# ComboBreaker.net
KiCad netlist of a schematic drawn in EAGLE
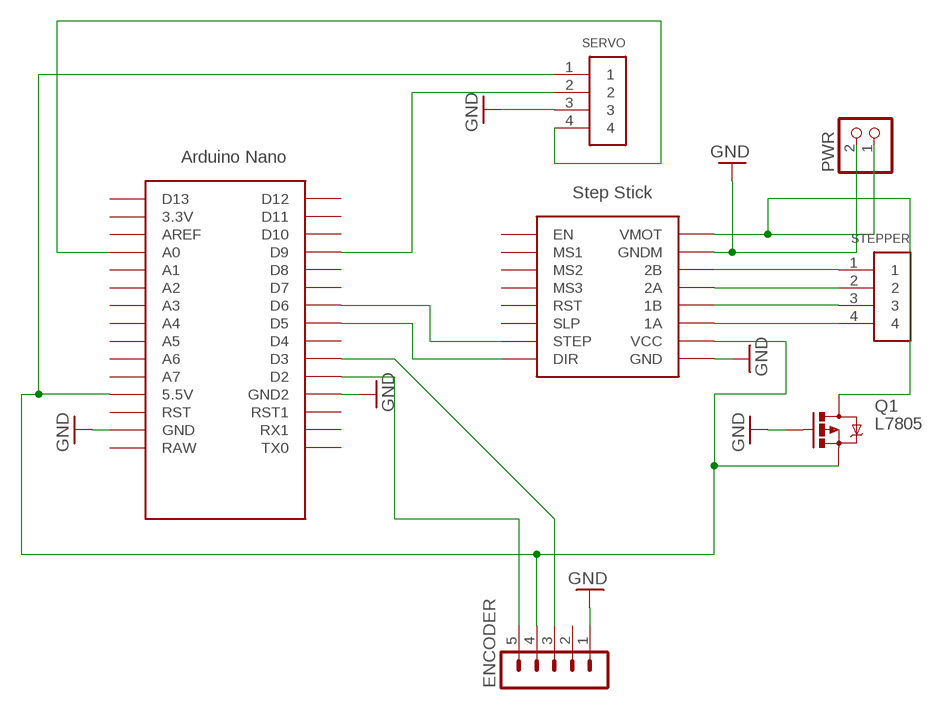
[diagram p0: schematic, sheet 1]

(export (version "E")
  (design (tool "Eeschema 10.0.6"))
  (components
    (comp (ref "ENCODER")
      (value "MA05-1")
      (footprint "eagle-import:MA05-1")
      (libsource (lib "eagle-import") (part "MA05-1"))
    )
    (comp (ref "PWR")
      (value "JST_2PIN-SMT")
      (footprint "eagle-import:JST-PH-2-SMT")
      (libsource (lib "eagle-import") (part "JST_2PIN-SMT"))
    )
    (comp (ref "Q1")
      (value "L7805")
      (footprint "eagle-import:TO220V")
      (libsource (lib "eagle-import") (part "MOSFET-PCHANNELFQP27P06"))
    )
    (comp (ref "SERVO")
      (value "1X4-BIG")
      (footprint "eagle-import:1X04-BIG")
      (libsource (lib "eagle-import") (part "1X4-BIG"))
    )
    (comp (ref "STEPPER")
      (value "1X4-BIG")
      (footprint "eagle-import:1X04-BIG")
      (libsource (lib "eagle-import") (part "1X4-BIG"))
    )
    (comp (ref "U$1")
      (value "NANO")
      (footprint "eagle-import:NANO")
      (libsource (lib "eagle-import") (part "NANO"))
    )
    (comp (ref "U$2")
      (value "STEP-STICK")
      (footprint "eagle-import:STEP-STICK")
      (libsource (lib "eagle-import") (part "STEP-STICK"))
    )
  )
  (nets
    (net (code "1") (name "GND") (class "Default")
      (node (ref "ENCODER") (pin "1") (pinfunction "1_1") (pintype "passive"))
      (node (ref "PWR") (pin "2") (pinfunction "1_2") (pintype "passive"))
      (node (ref "Q1") (pin "1") (pinfunction "G_1") (pintype "passive"))
      (node (ref "SERVO") (pin "3") (pinfunction "3_3") (pintype "bidirectional"))
      (node (ref "U$1") (pin "GND") (pinfunction "GND_GND") (pintype "bidirectional"))
      (node (ref "U$1") (pin "GND1") (pinfunction "GND2_GND1") (pintype "bidirectional"))
      (node (ref "U$2") (pin "GND") (pinfunction "GND_GND") (pintype "bidirectional"))
      (node (ref "U$2") (pin "GNDM") (pinfunction "GNDM_GNDM") (pintype "bidirectional"))
    )
    (net (code "2") (name "Net-(ENCODER-Pad3)") (class "Default")
      (node (ref "ENCODER") (pin "3") (pinfunction "3_3") (pintype "passive"))
      (node (ref "U$1") (pin "D3") (pinfunction "D3_D3") (pintype "bidirectional"))
    )
    (net (code "3") (name "Net-(ENCODER-Pad5)") (class "Default")
      (node (ref "ENCODER") (pin "5") (pinfunction "5_5") (pintype "passive"))
      (node (ref "U$1") (pin "D2") (pinfunction "D2_D2") (pintype "bidirectional"))
    )
    (net (code "4") (name "Net-(PWR-2)") (class "Default")
      (node (ref "PWR") (pin "1") (pinfunction "2_1") (pintype "passive"))
      (node (ref "Q1") (pin "2") (pinfunction "D_2") (pintype "passive"))
      (node (ref "U$2") (pin "VMOT") (pinfunction "VMOT_VMOT") (pintype "bidirectional"))
    )
    (net (code "5") (name "Net-(Q1-S)") (class "Default")
      (node (ref "ENCODER") (pin "4") (pinfunction "4_4") (pintype "passive"))
      (node (ref "Q1") (pin "3") (pinfunction "S_3") (pintype "passive"))
      (node (ref "SERVO") (pin "1") (pinfunction "1_1") (pintype "bidirectional"))
      (node (ref "U$1") (pin "5V") (pinfunction "5.5V_5V") (pintype "bidirectional"))
      (node (ref "U$2") (pin "VCC") (pinfunction "VCC_VCC") (pintype "bidirectional"))
    )
    (net (code "6") (name "Net-(SERVO-Pad2)") (class "Default")
      (node (ref "SERVO") (pin "2") (pinfunction "2_2") (pintype "bidirectional"))
      (node (ref "U$1") (pin "D9") (pinfunction "D9_D9") (pintype "bidirectional"))
    )
    (net (code "7") (name "Net-(SERVO-Pad4)") (class "Default")
      (node (ref "SERVO") (pin "4") (pinfunction "4_4") (pintype "bidirectional"))
      (node (ref "U$1") (pin "A0") (pinfunction "A0_A0") (pintype "bidirectional"))
    )
    (net (code "8") (name "Net-(STEPPER-Pad1)") (class "Default")
      (node (ref "STEPPER") (pin "1") (pinfunction "1_1") (pintype "bidirectional"))
      (node (ref "U$2") (pin "2B") (pinfunction "2B_2B") (pintype "bidirectional"))
    )
    (net (code "9") (name "Net-(STEPPER-Pad2)") (class "Default")
      (node (ref "STEPPER") (pin "2") (pinfunction "2_2") (pintype "bidirectional"))
      (node (ref "U$2") (pin "2A") (pinfunction "2A_2A") (pintype "bidirectional"))
    )
    (net (code "10") (name "Net-(STEPPER-Pad3)") (class "Default")
      (node (ref "STEPPER") (pin "3") (pinfunction "3_3") (pintype "bidirectional"))
      (node (ref "U$2") (pin "1B") (pinfunction "1B_1B") (pintype "bidirectional"))
    )
    (net (code "11") (name "Net-(STEPPER-Pad4)") (class "Default")
      (node (ref "STEPPER") (pin "4") (pinfunction "4_4") (pintype "bidirectional"))
      (node (ref "U$2") (pin "1A") (pinfunction "1A_1A") (pintype "bidirectional"))
    )
    (net (code "12") (name "Net-(U$1-PadD5)") (class "Default")
      (node (ref "U$1") (pin "D5") (pinfunction "D5_D5") (pintype "bidirectional"))
      (node (ref "U$2") (pin "DIR") (pinfunction "DIR_DIR") (pintype "bidirectional"))
    )
    (net (code "13") (name "Net-(U$2-STEP)") (class "Default")
      (node (ref "U$1") (pin "D6") (pinfunction "D6_D6") (pintype "bidirectional"))
      (node (ref "U$2") (pin "SPT") (pinfunction "STEP_SPT") (pintype "bidirectional"))
    )
    (net (code "14") (name "unconnected-(ENCODER-Pad2)") (class "Default")
      (node (ref "ENCODER") (pin "2") (pinfunction "2_2") (pintype "passive"))
    )
    (net (code "15") (name "unconnected-(U$1-Pad3.3V)") (class "Default")
      (node (ref "U$1") (pin "3.3V") (pinfunction "3.3V_3.3V") (pintype "bidirectional"))
    )
    (net (code "16") (name "unconnected-(U$1-PadA1)") (class "Default")
      (node (ref "U$1") (pin "A1") (pinfunction "A1_A1") (pintype "bidirectional"))
    )
    (net (code "17") (name "unconnected-(U$1-PadA2)") (class "Default")
      (node (ref "U$1") (pin "A2") (pinfunction "A2_A2") (pintype "bidirectional"))
    )
    (net (code "18") (name "unconnected-(U$1-PadA3)") (class "Default")
      (node (ref "U$1") (pin "A3") (pinfunction "A3_A3") (pintype "bidirectional"))
    )
    (net (code "19") (name "unconnected-(U$1-PadA4)") (class "Default")
      (node (ref "U$1") (pin "A4") (pinfunction "A4_A4") (pintype "bidirectional"))
    )
    (net (code "20") (name "unconnected-(U$1-PadA5)") (class "Default")
      (node (ref "U$1") (pin "A5") (pinfunction "A5_A5") (pintype "bidirectional"))
    )
    (net (code "21") (name "unconnected-(U$1-PadA6)") (class "Default")
      (node (ref "U$1") (pin "A6") (pinfunction "A6_A6") (pintype "bidirectional"))
    )
    (net (code "22") (name "unconnected-(U$1-PadA7)") (class "Default")
      (node (ref "U$1") (pin "A7") (pinfunction "A7_A7") (pintype "bidirectional"))
    )
    (net (code "23") (name "unconnected-(U$1-PadAREF)") (class "Default")
      (node (ref "U$1") (pin "AREF") (pinfunction "AREF_AREF") (pintype "bidirectional"))
    )
    (net (code "24") (name "unconnected-(U$1-PadD4)") (class "Default")
      (node (ref "U$1") (pin "D4") (pinfunction "D4_D4") (pintype "bidirectional"))
    )
    (net (code "25") (name "unconnected-(U$1-PadD7)") (class "Default")
      (node (ref "U$1") (pin "D7") (pinfunction "D7_D7") (pintype "bidirectional"))
    )
    (net (code "26") (name "unconnected-(U$1-PadD8)") (class "Default")
      (node (ref "U$1") (pin "D8") (pinfunction "D8_D8") (pintype "bidirectional"))
    )
    (net (code "27") (name "unconnected-(U$1-PadD10)") (class "Default")
      (node (ref "U$1") (pin "D10") (pinfunction "D10_D10") (pintype "bidirectional"))
    )
    (net (code "28") (name "unconnected-(U$1-PadD11)") (class "Default")
      (node (ref "U$1") (pin "D11") (pinfunction "D11_D11") (pintype "bidirectional"))
    )
    (net (code "29") (name "unconnected-(U$1-PadD12)") (class "Default")
      (node (ref "U$1") (pin "D12") (pinfunction "D12_D12") (pintype "bidirectional"))
    )
    (net (code "30") (name "unconnected-(U$1-PadD13)") (class "Default")
      (node (ref "U$1") (pin "D13") (pinfunction "D13_D13") (pintype "bidirectional"))
    )
    (net (code "31") (name "unconnected-(U$1-PadICSP1)") (class "Default")
      (node (ref "U$1") (pin "ICSP1") (pinfunction "ICSP1_ICSP1") (pintype "bidirectional"))
    )
    (net (code "32") (name "unconnected-(U$1-PadICSP2)") (class "Default")
      (node (ref "U$1") (pin "ICSP2") (pinfunction "ICSP2_ICSP2") (pintype "bidirectional"))
    )
    (net (code "33") (name "unconnected-(U$1-PadICSP3)") (class "Default")
      (node (ref "U$1") (pin "ICSP3") (pinfunction "ICSP3_ICSP3") (pintype "bidirectional"))
    )
    (net (code "34") (name "unconnected-(U$1-PadICSP4)") (class "Default")
      (node (ref "U$1") (pin "ICSP4") (pinfunction "ICSP4_ICSP4") (pintype "bidirectional"))
    )
    (net (code "35") (name "unconnected-(U$1-PadICSP5)") (class "Default")
      (node (ref "U$1") (pin "ICSP5") (pinfunction "ICSP5_ICSP5") (pintype "bidirectional"))
    )
    (net (code "36") (name "unconnected-(U$1-PadICSP6)") (class "Default")
      (node (ref "U$1") (pin "ICSP6") (pinfunction "ICSP6_ICSP6") (pintype "bidirectional"))
    )
    (net (code "37") (name "unconnected-(U$1-PadRAW)") (class "Default")
      (node (ref "U$1") (pin "RAW") (pinfunction "RAW_RAW") (pintype "bidirectional"))
    )
    (net (code "38") (name "unconnected-(U$1-PadRST)") (class "Default")
      (node (ref "U$1") (pin "RST") (pinfunction "RST_RST") (pintype "bidirectional"))
    )
    (net (code "39") (name "unconnected-(U$1-PadRST1)") (class "Default")
      (node (ref "U$1") (pin "RST1") (pinfunction "RST1_RST1") (pintype "bidirectional"))
    )
    (net (code "40") (name "unconnected-(U$1-PadRX1)") (class "Default")
      (node (ref "U$1") (pin "RX1") (pinfunction "RX1_RX1") (pintype "bidirectional"))
    )
    (net (code "41") (name "unconnected-(U$1-PadTX0)") (class "Default")
      (node (ref "U$1") (pin "TX0") (pinfunction "TX0_TX0") (pintype "bidirectional"))
    )
    (net (code "42") (name "unconnected-(U$2-PadEN)") (class "Default")
      (node (ref "U$2") (pin "EN") (pinfunction "EN_EN") (pintype "bidirectional"))
    )
    (net (code "43") (name "unconnected-(U$2-PadMS1)") (class "Default")
      (node (ref "U$2") (pin "MS1") (pinfunction "MS1_MS1") (pintype "bidirectional"))
    )
    (net (code "44") (name "unconnected-(U$2-PadMS2)") (class "Default")
      (node (ref "U$2") (pin "MS2") (pinfunction "MS2_MS2") (pintype "bidirectional"))
    )
    (net (code "45") (name "unconnected-(U$2-PadMS3)") (class "Default")
      (node (ref "U$2") (pin "MS3") (pinfunction "MS3_MS3") (pintype "bidirectional"))
    )
    (net (code "46") (name "unconnected-(U$2-PadRST)") (class "Default")
      (node (ref "U$2") (pin "RST") (pinfunction "RST_RST") (pintype "bidirectional"))
    )
    (net (code "47") (name "unconnected-(U$2-PadSLP)") (class "Default")
      (node (ref "U$2") (pin "SLP") (pinfunction "SLP_SLP") (pintype "bidirectional"))
    )
  )
)
